# untitled.net
KiCad netlist of a schematic drawn in EAGLE
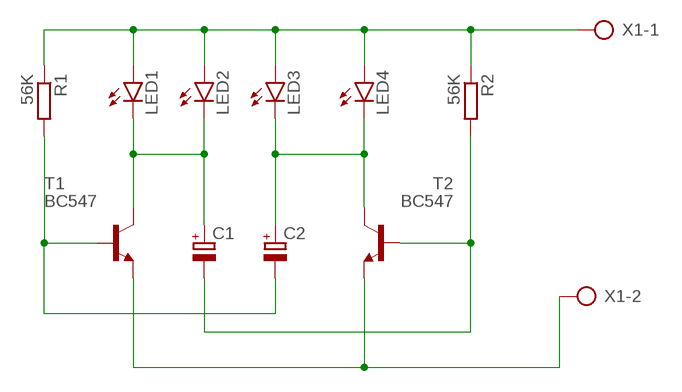
[diagram p0: schematic, sheet 1]

(export (version "E")
  (design (tool "Eeschema 10.0.6"))
  (components
    (comp (ref "C1")
      (value "CPOL-EUE2-4")
      (footprint "eagle-import:E2-4")
      (libsource (lib "eagle-import") (part "CPOL-EUE2-4"))
    )
    (comp (ref "C2")
      (value "CPOL-EUE2-4")
      (footprint "eagle-import:E2-4")
      (libsource (lib "eagle-import") (part "CPOL-EUE2-4"))
    )
    (comp (ref "LED1")
      (value "LED3MM")
      (footprint "eagle-import:LED3MM")
      (libsource (lib "eagle-import") (part "LED3MM"))
    )
    (comp (ref "LED2")
      (value "LED3MM")
      (footprint "eagle-import:LED3MM")
      (libsource (lib "eagle-import") (part "LED3MM"))
    )
    (comp (ref "LED3")
      (value "LED3MM")
      (footprint "eagle-import:LED3MM")
      (libsource (lib "eagle-import") (part "LED3MM"))
    )
    (comp (ref "LED4")
      (value "LED3MM")
      (footprint "eagle-import:LED3MM")
      (libsource (lib "eagle-import") (part "LED3MM"))
    )
    (comp (ref "R1")
      (value "56K")
      (footprint "eagle-import:0204_7")
      (libsource (lib "eagle-import") (part "R-EU_0204/7"))
    )
    (comp (ref "R2")
      (value "56K")
      (footprint "eagle-import:0204_7")
      (libsource (lib "eagle-import") (part "R-EU_0204/7"))
    )
    (comp (ref "T1")
      (value "BC547")
      (footprint "eagle-import:TO92")
      (libsource (lib "eagle-import") (part "BC547"))
    )
    (comp (ref "T2")
      (value "BC547")
      (footprint "eagle-import:TO92")
      (libsource (lib "eagle-import") (part "BC547"))
    )
    (comp (ref "X1")
      (value "AK300/2")
      (footprint "eagle-import:AK300_2")
      (libsource (lib "eagle-import") (part "AK300/2"))
    )
  )
  (nets
    (net (code "1") (name "Net-(LED1-C)") (class "Default")
      (node (ref "C1") (pin "+") (pinfunction "+_+") (pintype "passive"))
      (node (ref "LED1") (pin "K") (pinfunction "C_K") (pintype "passive"))
      (node (ref "LED2") (pin "K") (pinfunction "C_K") (pintype "passive"))
      (node (ref "T1") (pin "3") (pinfunction "C_3") (pintype "passive"))
    )
    (net (code "2") (name "Net-(LED3-C)") (class "Default")
      (node (ref "C2") (pin "+") (pinfunction "+_+") (pintype "passive"))
      (node (ref "LED3") (pin "K") (pinfunction "C_K") (pintype "passive"))
      (node (ref "LED4") (pin "K") (pinfunction "C_K") (pintype "passive"))
      (node (ref "T2") (pin "3") (pinfunction "C_3") (pintype "passive"))
    )
    (net (code "3") (name "Net-(T1-B)") (class "Default")
      (node (ref "C2") (pin "-") (pinfunction "-_-") (pintype "passive"))
      (node (ref "R1") (pin "2") (pinfunction "2_2") (pintype "passive"))
      (node (ref "T1") (pin "2") (pinfunction "B_2") (pintype "passive"))
    )
    (net (code "4") (name "Net-(T1-E)") (class "Default")
      (node (ref "T1") (pin "1") (pinfunction "E_1") (pintype "passive"))
      (node (ref "T2") (pin "1") (pinfunction "E_1") (pintype "passive"))
      (node (ref "X1") (pin "2") (pinfunction "KL_2") (pintype "passive"))
    )
    (net (code "5") (name "Net-(T2-B)") (class "Default")
      (node (ref "C1") (pin "-") (pinfunction "-_-") (pintype "passive"))
      (node (ref "R2") (pin "2") (pinfunction "2_2") (pintype "passive"))
      (node (ref "T2") (pin "2") (pinfunction "B_2") (pintype "passive"))
    )
    (net (code "6") (name "Net-(X1A-KL)") (class "Default")
      (node (ref "LED1") (pin "A") (pinfunction "A_A") (pintype "passive"))
      (node (ref "LED2") (pin "A") (pinfunction "A_A") (pintype "passive"))
      (node (ref "LED3") (pin "A") (pinfunction "A_A") (pintype "passive"))
      (node (ref "LED4") (pin "A") (pinfunction "A_A") (pintype "passive"))
      (node (ref "R1") (pin "1") (pinfunction "1_1") (pintype "passive"))
      (node (ref "R2") (pin "1") (pinfunction "1_1") (pintype "passive"))
      (node (ref "X1") (pin "1") (pinfunction "KL_1") (pintype "passive"))
    )
  )
)
